# Codec.net
KiCad netlist of a schematic drawn in Altium Designer
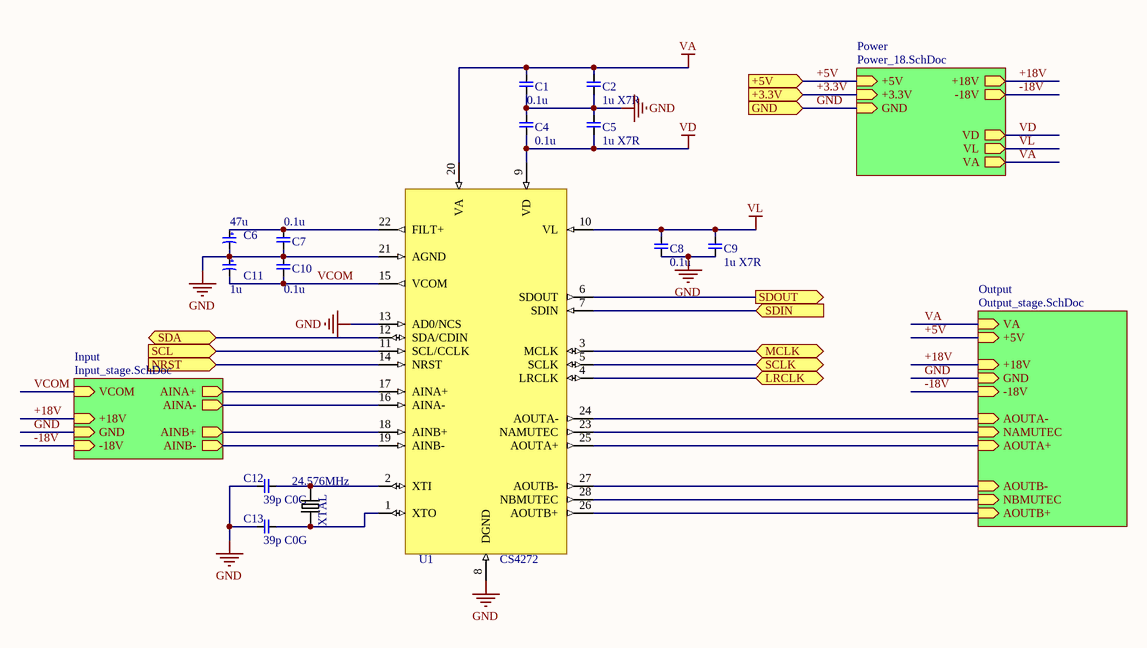
[diagram p0: Codec.SchDoc]

(export (version "E")
  (design (tool "Eeschema 10.0.6"))
  (components
    (comp (ref "24.576MHz")
      (value "XTAL")
      (footprint "XTAL_hc-49_smd")
      (description "Crystal 4MHz ?30ppm (Tol) ?50ppm (Stability) 20pF FUND 200Ohm 2-Pin HC-49/SDLF SMD T/R")
      (fields (field (name "MP") "FOXSDLF/040") (field (name "MF") "Fox Electronics"))
      (libsource (lib "Codec_board") (part "hc-49_smd"))
    )
    (comp (ref "C1") (value "0.1u") (footprint "0805_cap") (libsource (lib "Codec_board") (part "Cap")))
    (comp (ref "C2") (value "1u X7R") (footprint "0805_cap") (libsource (lib "Codec_board") (part "Cap")))
    (comp (ref "C4") (value "0.1u") (footprint "0805_cap") (libsource (lib "Codec_board") (part "Cap")))
    (comp (ref "C5") (value "1u X7R") (footprint "0805_cap") (libsource (lib "Codec_board") (part "Cap")))
    (comp (ref "C6")
      (value "47u")
      (footprint "cap 4x5.4")
      (libsource (lib "Codec_board") (part "Cap_electrolytic"))
    )
    (comp (ref "C7") (value "0.1u") (footprint "0805_cap") (libsource (lib "Codec_board") (part "Cap")))
    (comp (ref "C8") (value "0.1u") (footprint "0805_cap") (libsource (lib "Codec_board") (part "Cap")))
    (comp (ref "C9") (value "1u X7R") (footprint "0805_cap") (libsource (lib "Codec_board") (part "Cap")))
    (comp (ref "C10") (value "0.1u") (footprint "0805_cap") (libsource (lib "Codec_board") (part "Cap")))
    (comp (ref "C11")
      (value "1u")
      (footprint "cap 4x5.4")
      (libsource (lib "Codec_board") (part "Cap_electrolytic"))
    )
    (comp (ref "C12") (value "39p C0G") (footprint "0805_cap") (libsource (lib "Codec_board") (part "Cap")))
    (comp (ref "C13") (value "39p C0G") (footprint "0805_cap") (libsource (lib "Codec_board") (part "Cap")))
    (comp (ref "U1") (value "CS4272") (footprint "TSSOP-28") (libsource (lib "Codec_board") (part "CS4272")))
  )
  (nets
    (net (code "5") (name "/AINA+") (class "Default")
      (node (ref "U1") (pin "17") (pinfunction "AINA+_17") (pintype "input"))
    )
    (net (code "6") (name "/AINA-") (class "Default")
      (node (ref "U1") (pin "16") (pinfunction "AINA-_16") (pintype "input"))
    )
    (net (code "7") (name "/AINB+") (class "Default")
      (node (ref "U1") (pin "18") (pinfunction "AINB+_18") (pintype "input"))
    )
    (net (code "8") (name "/AINB-") (class "Default")
      (node (ref "U1") (pin "19") (pinfunction "AINB-_19") (pintype "input"))
    )
    (net (code "9") (name "/AOUTA+") (class "Default")
      (node (ref "U1") (pin "25") (pinfunction "AOUTA+_25") (pintype "output"))
    )
    (net (code "10") (name "/AOUTA-") (class "Default")
      (node (ref "U1") (pin "24") (pinfunction "AOUTA-_24") (pintype "output"))
    )
    (net (code "11") (name "/AOUTB+") (class "Default")
      (node (ref "U1") (pin "26") (pinfunction "AOUTB+_26") (pintype "output"))
    )
    (net (code "12") (name "/AOUTB-") (class "Default")
      (node (ref "U1") (pin "27") (pinfunction "AOUTB-_27") (pintype "output"))
    )
    (net (code "13") (name "/LRCLK") (class "Default")
      (node (ref "U1") (pin "4") (pinfunction "LRCLK_4") (pintype "bidirectional"))
    )
    (net (code "14") (name "/MCLK") (class "Default")
      (node (ref "U1") (pin "3") (pinfunction "MCLK_3") (pintype "bidirectional"))
    )
    (net (code "15") (name "/NAMUTEC") (class "Default")
      (node (ref "U1") (pin "23") (pinfunction "NAMUTEC_23") (pintype "output"))
    )
    (net (code "16") (name "/NBMUTEC") (class "Default")
      (node (ref "U1") (pin "28") (pinfunction "NBMUTEC_28") (pintype "output"))
    )
    (net (code "17") (name "/NRST") (class "Default")
      (node (ref "U1") (pin "14") (pinfunction "NRST_14") (pintype "input"))
    )
    (net (code "18") (name "/SCL") (class "Default")
      (node (ref "U1") (pin "11") (pinfunction "SCL/CCLK_11") (pintype "input"))
    )
    (net (code "19") (name "/SCLK") (class "Default")
      (node (ref "U1") (pin "5") (pinfunction "SCLK_5") (pintype "bidirectional"))
    )
    (net (code "20") (name "/SDA") (class "Default")
      (node (ref "U1") (pin "12") (pinfunction "SDA/CDIN_12") (pintype "bidirectional"))
    )
    (net (code "21") (name "/SDIN") (class "Default")
      (node (ref "U1") (pin "7") (pinfunction "SDIN_7") (pintype "input"))
    )
    (net (code "22") (name "/SDOUT") (class "Default")
      (node (ref "U1") (pin "6") (pinfunction "SDOUT_6") (pintype "output"))
    )
    (net (code "23") (name "/VCOM") (class "Default")
      (node (ref "C10") (pin "1") (pinfunction "1_1") (pintype "passive"))
      (node (ref "C11") (pin "2") (pinfunction "2_2") (pintype "passive"))
      (node (ref "U1") (pin "15") (pinfunction "VCOM_15") (pintype "output"))
    )
    (net (code "24") (name "GND") (class "Default")
      (node (ref "C1") (pin "1") (pinfunction "1_1") (pintype "passive"))
      (node (ref "C10") (pin "2") (pinfunction "2_2") (pintype "passive"))
      (node (ref "C11") (pin "1") (pinfunction "1_1") (pintype "passive"))
      (node (ref "C12") (pin "1") (pinfunction "1_1") (pintype "passive"))
      (node (ref "C13") (pin "1") (pinfunction "1_1") (pintype "passive"))
      (node (ref "C2") (pin "1") (pinfunction "1_1") (pintype "passive"))
      (node (ref "C4") (pin "2") (pinfunction "2_2") (pintype "passive"))
      (node (ref "C5") (pin "2") (pinfunction "2_2") (pintype "passive"))
      (node (ref "C6") (pin "2") (pinfunction "2_2") (pintype "passive"))
      (node (ref "C7") (pin "1") (pinfunction "1_1") (pintype "passive"))
      (node (ref "C8") (pin "1") (pinfunction "1_1") (pintype "passive"))
      (node (ref "C9") (pin "1") (pinfunction "1_1") (pintype "passive"))
      (node (ref "U1") (pin "13") (pinfunction "AD0/NCS_13") (pintype "input"))
      (node (ref "U1") (pin "21") (pinfunction "AGND_21") (pintype "input"))
      (node (ref "U1") (pin "8") (pinfunction "DGND_8") (pintype "input"))
    )
    (net (code "25") (name "Net-(U1-FILT+)") (class "Default")
      (node (ref "C6") (pin "1") (pinfunction "1_1") (pintype "passive"))
      (node (ref "C7") (pin "2") (pinfunction "2_2") (pintype "passive"))
      (node (ref "U1") (pin "22") (pinfunction "FILT+_22") (pintype "output"))
    )
    (net (code "26") (name "Net-(U1-XTI)") (class "Default")
      (node (ref "24.576MHz") (pin "2") (pinfunction "2_2") (pintype "passive"))
      (node (ref "C12") (pin "2") (pinfunction "2_2") (pintype "passive"))
      (node (ref "U1") (pin "2") (pinfunction "XTI_2") (pintype "bidirectional"))
    )
    (net (code "27") (name "Net-(U1-XTO)") (class "Default")
      (node (ref "24.576MHz") (pin "1") (pinfunction "1_1") (pintype "passive"))
      (node (ref "C13") (pin "2") (pinfunction "2_2") (pintype "passive"))
      (node (ref "U1") (pin "1") (pinfunction "XTO_1") (pintype "bidirectional"))
    )
    (net (code "28") (name "VA") (class "Default")
      (node (ref "C1") (pin "2") (pinfunction "2_2") (pintype "passive"))
      (node (ref "C2") (pin "2") (pinfunction "2_2") (pintype "passive"))
      (node (ref "U1") (pin "20") (pinfunction "VA_20") (pintype "input"))
    )
    (net (code "29") (name "VD") (class "Default")
      (node (ref "C4") (pin "1") (pinfunction "1_1") (pintype "passive"))
      (node (ref "C5") (pin "1") (pinfunction "1_1") (pintype "passive"))
      (node (ref "U1") (pin "9") (pinfunction "VD_9") (pintype "input"))
    )
    (net (code "30") (name "VL") (class "Default")
      (node (ref "C8") (pin "2") (pinfunction "2_2") (pintype "passive"))
      (node (ref "C9") (pin "2") (pinfunction "2_2") (pintype "passive"))
      (node (ref "U1") (pin "10") (pinfunction "VL_10") (pintype "input"))
    )
  )
)
